# Kortex_Agro.net
KiCad netlist of a schematic drawn in EAGLE
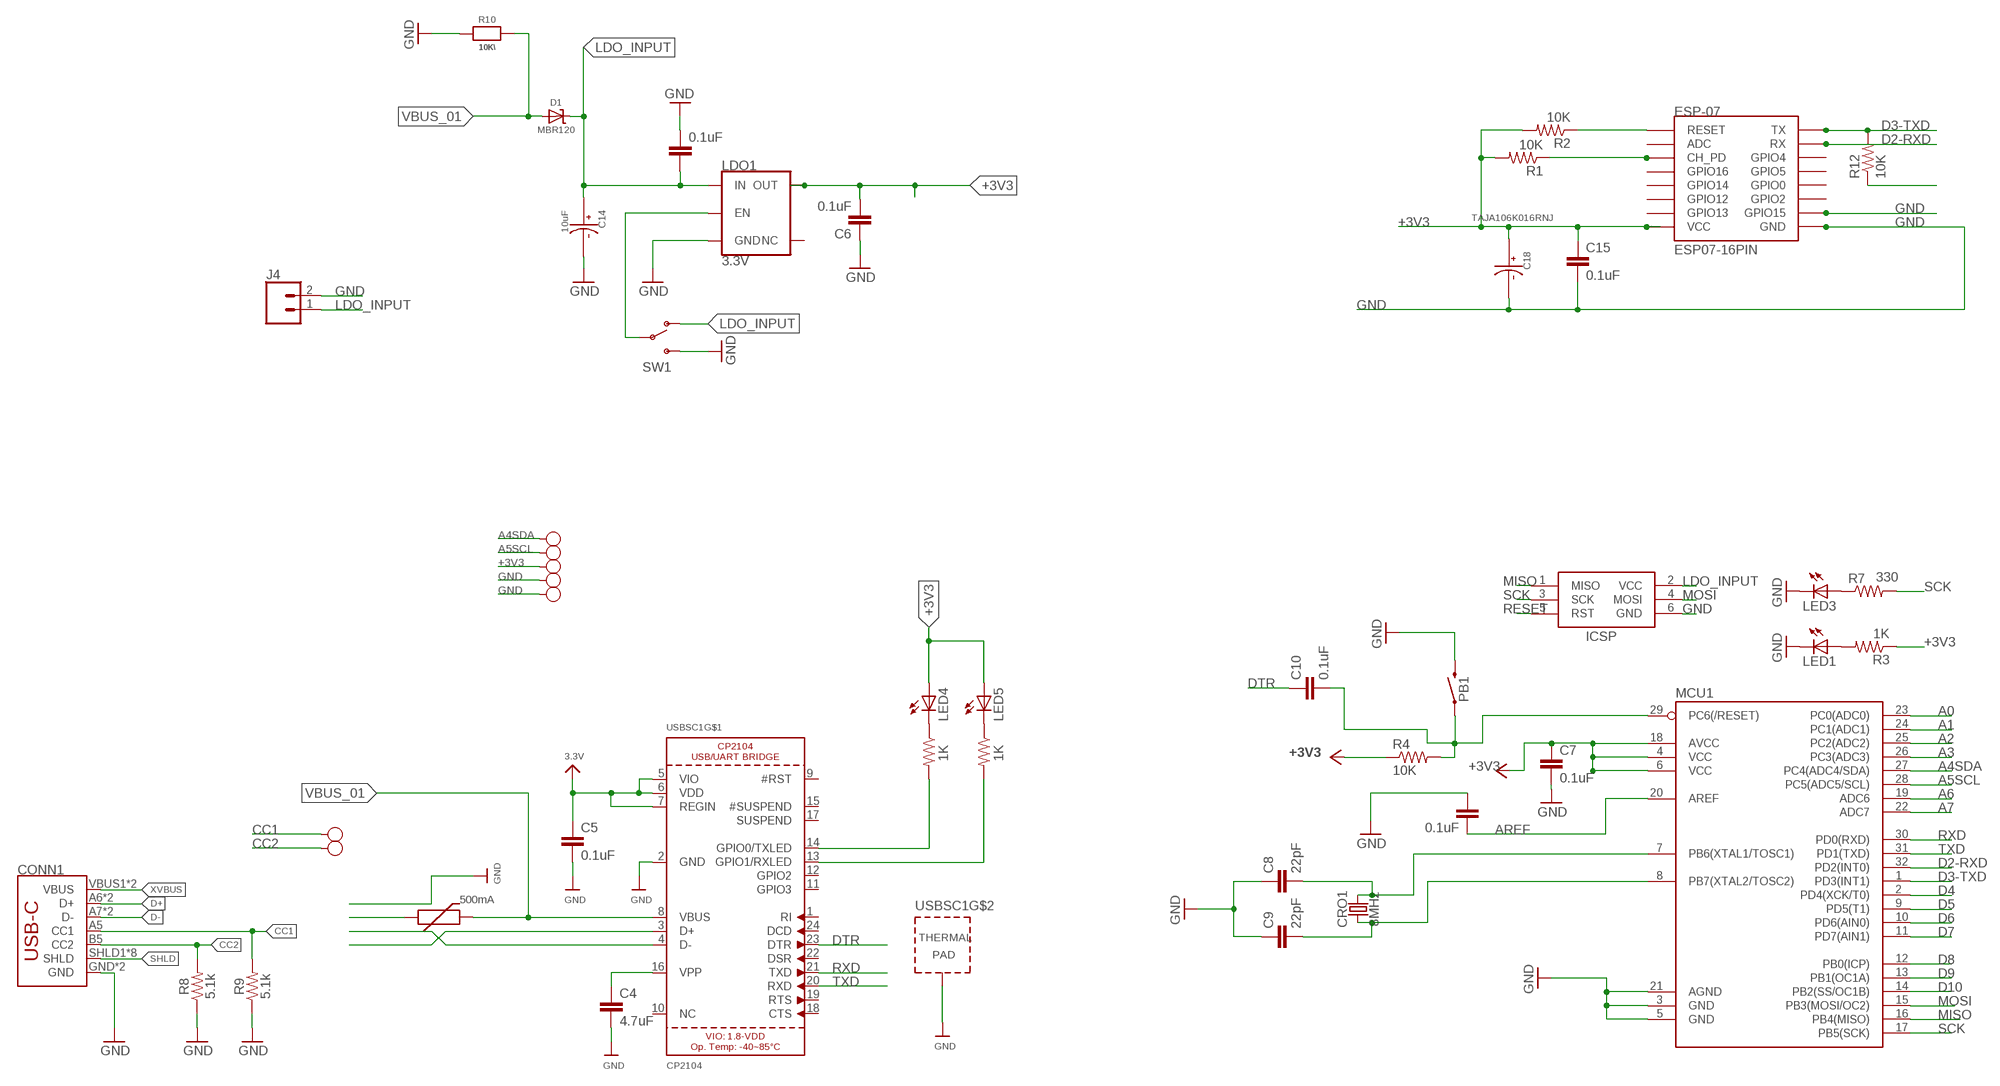
[diagram p0: schematic, sheet 1, part 1 of 2]
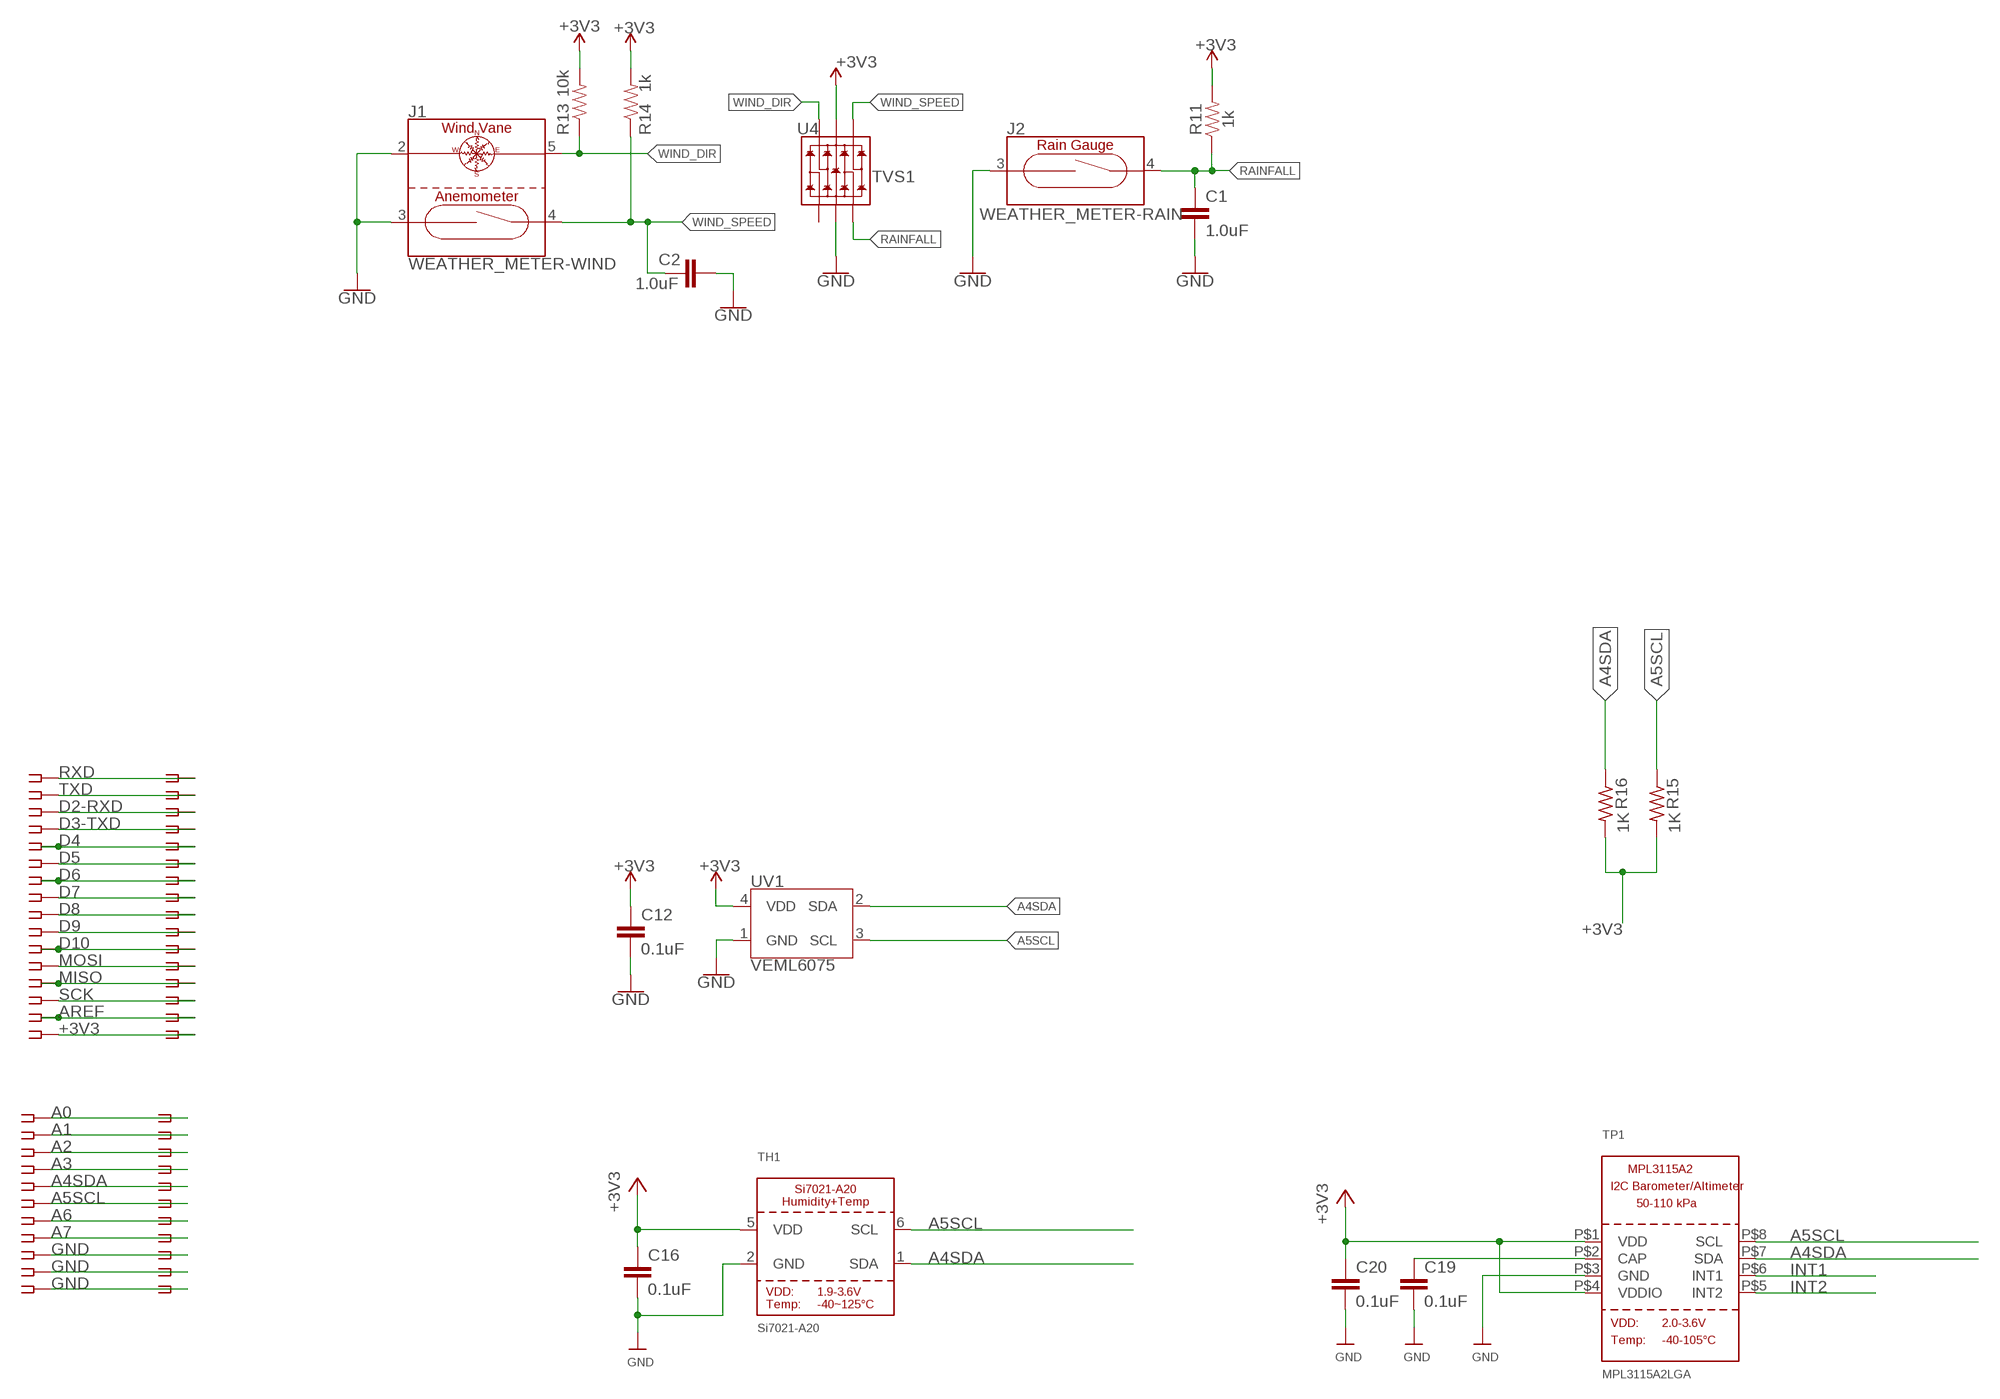
[diagram p1: schematic, sheet 1, part 2 of 2]

(export (version "E")
  (design (tool "Eeschema 10.0.6"))
  (components
    (comp (ref "+3.3V")
      (value "+3V3")
      (footprint "eagle-import:TP-D45MIL")
      (fields (field (name "PARTNO") "DNP"))
      (libsource (lib "eagle-import") (part "TEST-POINT'4545'"))
    )
    (comp (ref "C1")
      (value "1.0uF")
      (footprint "eagle-import:0603")
      (libsource (lib "eagle-import") (part "1.0UF-0603-16V-10%"))
    )
    (comp (ref "C2")
      (value "1.0uF")
      (footprint "eagle-import:0603")
      (libsource (lib "eagle-import") (part "1.0UF-0603-16V-10%"))
    )
    (comp (ref "C3")
      (value "0.1uF")
      (footprint "eagle-import:0805")
      (libsource (lib "eagle-import") (part "22UF-0805-6.3V-20%"))
    )
    (comp (ref "C4")
      (value "4.7uF")
      (footprint "eagle-import:0805")
      (libsource (lib "eagle-import") (part "22UF-0805-6.3V-20%"))
    )
    (comp (ref "C5")
      (value "0.1uF")
      (footprint "eagle-import:0805")
      (libsource (lib "eagle-import") (part "22UF-0805-6.3V-20%"))
    )
    (comp (ref "C6")
      (value "0.1uF")
      (footprint "eagle-import:0805")
      (libsource (lib "eagle-import") (part "22UF-0805-6.3V-20%"))
    )
    (comp (ref "C7")
      (value "0.1uF")
      (footprint "eagle-import:0805")
      (libsource (lib "eagle-import") (part "22UF-0805-6.3V-20%"))
    )
    (comp (ref "C8")
      (value "22pF")
      (footprint "eagle-import:0805")
      (libsource (lib "eagle-import") (part "22UF-0805-6.3V-20%"))
    )
    (comp (ref "C9")
      (value "22pF")
      (footprint "eagle-import:0805")
      (libsource (lib "eagle-import") (part "22UF-0805-6.3V-20%"))
    )
    (comp (ref "C10")
      (value "0.1uF")
      (footprint "eagle-import:0805")
      (libsource (lib "eagle-import") (part "22UF-0805-6.3V-20%"))
    )
    (comp (ref "C11")
      (value "0.1uF")
      (footprint "eagle-import:0805")
      (libsource (lib "eagle-import") (part "22UF-0805-6.3V-20%"))
    )
    (comp (ref "C12")
      (value "0.1uF")
      (footprint "eagle-import:0603")
      (libsource (lib "eagle-import") (part "0.1UF-0603-25V-(+80/-20%)"))
    )
    (comp (ref "C14")
      (value "10uF")
      (footprint "eagle-import:CAPMP3216X166")
      (fields (field (name "MF") "AVX Interconnect / Elco") (field (name "MP") "TAJA106K016RNJ"))
      (libsource (lib "eagle-import") (part "TAJA106K016RNJ"))
    )
    (comp (ref "C15")
      (value "0.1uF")
      (footprint "eagle-import:0805")
      (libsource (lib "eagle-import") (part "CAP0805"))
    )
    (comp (ref "C16")
      (value "0.1uF")
      (footprint "eagle-import:0805")
      (libsource (lib "eagle-import") (part "SparkFun-Passives_CAP0805"))
    )
    (comp (ref "C18")
      (value "TAJA106K016RNJ")
      (footprint "eagle-import:CAPMP3216X166")
      (fields (field (name "MF") "AVX Interconnect / Elco"))
      (libsource (lib "eagle-import") (part "TAJA106K016RNJ"))
    )
    (comp (ref "C19")
      (value "0.1uF")
      (footprint "eagle-import:0805")
      (libsource (lib "eagle-import") (part "SparkFun-Passives_CAP0805"))
    )
    (comp (ref "C20")
      (value "0.1uF")
      (footprint "eagle-import:0805")
      (libsource (lib "eagle-import") (part "SparkFun-Passives_CAP0805"))
    )
    (comp (ref "CONN1")
      (value "USB_C16PIN")
      (footprint "eagle-import:USB-C-16P")
      (libsource (lib "eagle-import") (part "USB_C16PIN"))
    )
    (comp (ref "CRO1")
      (value "8MHz")
      (footprint "eagle-import:CRYSTAL-SMD-5X3.2-4PAD")
      (libsource (lib "eagle-import") (part "CRYSTAL-8MHZSMD-5X3.2"))
    )
    (comp (ref "D1")
      (value "MBR120")
      (footprint "eagle-import:SOD-123")
      (libsource (lib "eagle-import") (part "DIODE-SCHOTTKYSOD-123"))
    )
    (comp (ref "ESP-07")
      (value "ESP07-16PIN")
      (footprint "eagle-import:ESP07-16PIN")
      (libsource (lib "eagle-import") (part "ESP07-16PIN"))
    )
    (comp (ref "GND")
      (value "GND")
      (footprint "eagle-import:TP-D45MIL")
      (fields (field (name "PARTNO") "DNP"))
      (libsource (lib "eagle-import") (part "TEST-POINT'4545'"))
    )
    (comp (ref "GND13")
      (value "GND")
      (footprint "eagle-import:TP-D45MIL")
      (fields (field (name "PARTNO") "DNP"))
      (libsource (lib "eagle-import") (part "TEST-POINT'4545'"))
    )
    (comp (ref "GND21")
      (value "GND")
      (footprint "eagle-import:TP-D45MIL")
      (fields (field (name "PARTNO") "DNP"))
      (libsource (lib "eagle-import") (part "TEST-POINT'4545'"))
    )
    (comp (ref "GND22")
      (value "GND")
      (footprint "eagle-import:TP-D45MIL")
      (fields (field (name "PARTNO") "DNP"))
      (libsource (lib "eagle-import") (part "TEST-POINT'4545'"))
    )
    (comp (ref "HD1")
      (value "SSW-116-02-G-D")
      (footprint "eagle-import:SSW-116-02-G-D")
      (fields (field (name "MF") "Samtec Inc."))
      (libsource (lib "eagle-import") (part "SSW-116-02-G-D"))
    )
    (comp (ref "HD2")
      (value "SSW-111-02-S-D")
      (footprint "eagle-import:SSW-111-02-S-D")
      (libsource (lib "eagle-import") (part "SSW-111-02-S-D"))
    )
    (comp (ref "ICSP")
      (value "AVRISP-6")
      (footprint "eagle-import:AVRISP")
      (libsource (lib "eagle-import") (part "AVRISP-6"))
    )
    (comp (ref "J1")
      (value "WEATHER_METER-WIND")
      (footprint "eagle-import:RJ11-6")
      (libsource (lib "eagle-import") (part "WEATHER_METER-WIND"))
    )
    (comp (ref "J2")
      (value "WEATHER_METER-RAIN")
      (footprint "eagle-import:RJ11-6")
      (libsource (lib "eagle-import") (part "WEATHER_METER-RAIN"))
    )
    (comp (ref "J4")
      (value "CONN_02")
      (footprint "eagle-import:1X02")
      (libsource (lib "eagle-import") (part "CONN_02"))
    )
    (comp (ref "LDO1")
      (value "3.3V")
      (footprint "eagle-import:SOT23-5")
      (libsource (lib "eagle-import") (part "V_REG_AP2112K-3.3V"))
    )
    (comp (ref "LED1")
      (value "LEDCHIPLED_0805")
      (footprint "eagle-import:CHIPLED_0805")
      (libsource (lib "eagle-import") (part "LEDCHIPLED_0805"))
    )
    (comp (ref "LED3")
      (value "LEDCHIPLED_0805")
      (footprint "eagle-import:CHIPLED_0805")
      (libsource (lib "eagle-import") (part "LEDCHIPLED_0805"))
    )
    (comp (ref "LED4")
      (value "LEDCHIPLED_0805")
      (footprint "eagle-import:CHIPLED_0805")
      (libsource (lib "eagle-import") (part "LEDCHIPLED_0805"))
    )
    (comp (ref "LED5")
      (value "LEDCHIPLED_0805")
      (footprint "eagle-import:CHIPLED_0805")
      (libsource (lib "eagle-import") (part "LEDCHIPLED_0805"))
    )
    (comp (ref "MCU1")
      (value "ATMEGA328P_TQFPATMEGA328P-AU")
      (footprint "eagle-import:QFP80P912X912X120-32")
      (libsource (lib "eagle-import") (part "ATMEGA328P_TQFPATMEGA328P-AU"))
    )
    (comp (ref "PB1")
      (value "SWITCH-MOMENTARY-2SMD")
      (footprint "eagle-import:TACTILE_SWITCH_SMD")
      (libsource (lib "eagle-import") (part "SWITCH-MOMENTARY-2SMD"))
    )
    (comp (ref "PTC1")
      (value "500mA")
      (footprint "eagle-import:PTC-1206")
      (libsource (lib "eagle-import") (part "PTCSMD"))
    )
    (comp (ref "R1")
      (value "10K")
      (footprint "eagle-import:M0805")
      (libsource (lib "eagle-import") (part "resistor_R-US_M0805"))
    )
    (comp (ref "R2")
      (value "10K")
      (footprint "eagle-import:M0805")
      (libsource (lib "eagle-import") (part "resistor_R-US_M0805"))
    )
    (comp (ref "R3")
      (value "1K")
      (footprint "eagle-import:M0805")
      (libsource (lib "eagle-import") (part "R-US_M0805"))
    )
    (comp (ref "R4")
      (value "10K")
      (footprint "eagle-import:M0805")
      (libsource (lib "eagle-import") (part "R-US_M0805"))
    )
    (comp (ref "R5")
      (value "1K")
      (footprint "eagle-import:M0805")
      (libsource (lib "eagle-import") (part "R-US_M0805"))
    )
    (comp (ref "R6")
      (value "1K")
      (footprint "eagle-import:M0805")
      (libsource (lib "eagle-import") (part "R-US_M0805"))
    )
    (comp (ref "R7")
      (value "330")
      (footprint "eagle-import:M0805")
      (libsource (lib "eagle-import") (part "R-US_M0805"))
    )
    (comp (ref "R8")
      (value "5.1k")
      (footprint "eagle-import:0603")
      (libsource (lib "eagle-import") (part "5.1KOHM5.1KOHM-0603-1/10W-1%"))
    )
    (comp (ref "R9")
      (value "5.1k")
      (footprint "eagle-import:0603")
      (libsource (lib "eagle-import") (part "5.1KOHM5.1KOHM-0603-1/10W-1%"))
    )
    (comp (ref "R10")
      (value "10K\\")
      (footprint "eagle-import:0805-NO")
      (libsource (lib "eagle-import") (part "RESISTOR0805_NOOUTLINE"))
    )
    (comp (ref "R11")
      (value "1k")
      (footprint "eagle-import:0603")
      (libsource (lib "eagle-import") (part "1KOHM-0603-1/10W-1%"))
    )
    (comp (ref "R12")
      (value "10K")
      (footprint "eagle-import:M0805")
      (libsource (lib "eagle-import") (part "resistor_R-US_M0805"))
    )
    (comp (ref "R13")
      (value "10k")
      (footprint "eagle-import:0603")
      (libsource (lib "eagle-import") (part "10KOHM-0603-1/10W-1%"))
    )
    (comp (ref "R14")
      (value "1k")
      (footprint "eagle-import:0603")
      (libsource (lib "eagle-import") (part "1KOHM-0603-1/10W-1%"))
    )
    (comp (ref "R15")
      (value "1K")
      (footprint "eagle-import:M0805")
      (libsource (lib "eagle-import") (part "R-US_M0805"))
    )
    (comp (ref "R16")
      (value "1K")
      (footprint "eagle-import:M0805")
      (libsource (lib "eagle-import") (part "R-US_M0805"))
    )
    (comp (ref "SCL")
      (value "SCL")
      (footprint "eagle-import:TP-D45MIL")
      (fields (field (name "PARTNO") "DNP"))
      (libsource (lib "eagle-import") (part "TEST-POINT'4545'"))
    )
    (comp (ref "SDA")
      (value "SDA")
      (footprint "eagle-import:TP-D45MIL")
      (fields (field (name "PARTNO") "DNP"))
      (libsource (lib "eagle-import") (part "TEST-POINT'4545'"))
    )
    (comp (ref "SW1")
      (value "SWITCH-SPSTSMD")
      (footprint "eagle-import:AYZ0202")
      (libsource (lib "eagle-import") (part "SWITCH-SPSTSMD"))
    )
    (comp (ref "TH1")
      (value "Si7021-A20")
      (footprint "eagle-import:DFN6_3X3_SI")
      (libsource (lib "eagle-import") (part "SI7021-A20"))
    )
    (comp (ref "TP1")
      (value "MPL3115A2LGA")
      (footprint "eagle-import:LGA8")
      (libsource (lib "eagle-import") (part "MPL3115A2LGA"))
    )
    (comp (ref "U4")
      (value "TVS1")
      (footprint "eagle-import:SOT-23-6")
      (libsource (lib "eagle-import") (part "TVS_DIODE_ARRAYSMD"))
    )
    (comp (ref "USBSC1")
      (value "CP2104")
      (footprint "eagle-import:QFN24_4MM_SMSC")
      (fields (field (name "SPICEPREFIX") "X"))
      (libsource (lib "eagle-import") (part "CP2104"))
    )
    (comp (ref "UV1")
      (value "VEML6075")
      (footprint "eagle-import:VEML6075_A3OP")
      (libsource (lib "eagle-import") (part "VEML6075"))
    )
  )
  (nets
    (net (code "1") (name "+3V3") (class "Default")
      (node (ref "+3.3V") (pin "T") (pinfunction "T_T") (pintype "bidirectional"))
      (node (ref "C12") (pin "1") (pinfunction "1_1") (pintype "passive"))
      (node (ref "C15") (pin "1") (pinfunction "1_1") (pintype "passive"))
      (node (ref "C16") (pin "1") (pinfunction "1_1") (pintype "passive"))
      (node (ref "C18") (pin "+") (pinfunction "+_+") (pintype "passive"))
      (node (ref "C20") (pin "1") (pinfunction "1_1") (pintype "passive"))
      (node (ref "C5") (pin "1") (pinfunction "1_1") (pintype "passive"))
      (node (ref "C6") (pin "2") (pinfunction "2_2") (pintype "passive"))
      (node (ref "C7") (pin "1") (pinfunction "1_1") (pintype "passive"))
      (node (ref "ESP-07") (pin "VCC") (pinfunction "VCC_VCC") (pintype "bidirectional"))
      (node (ref "HD1") (pin "31") (pinfunction "1_31") (pintype "passive"))
      (node (ref "HD1") (pin "32") (pinfunction "1_32") (pintype "passive"))
      (node (ref "LDO1") (pin "5") (pinfunction "OUT_5") (pintype "passive"))
      (node (ref "LED4") (pin "A") (pinfunction "A_A") (pintype "passive"))
      (node (ref "LED5") (pin "A") (pinfunction "A_A") (pintype "passive"))
      (node (ref "MCU1") (pin "18") (pinfunction "AVCC_18") (pintype "bidirectional"))
      (node (ref "MCU1") (pin "4") (pinfunction "VCC_4") (pintype "bidirectional"))
      (node (ref "MCU1") (pin "6") (pinfunction "VCC_6") (pintype "bidirectional"))
      (node (ref "R1") (pin "2") (pinfunction "2_2") (pintype "passive"))
      (node (ref "R11") (pin "2") (pinfunction "2_2") (pintype "passive"))
      (node (ref "R13") (pin "2") (pinfunction "2_2") (pintype "passive"))
      (node (ref "R14") (pin "2") (pinfunction "2_2") (pintype "passive"))
      (node (ref "R15") (pin "2") (pinfunction "2_2") (pintype "passive"))
      (node (ref "R16") (pin "2") (pinfunction "2_2") (pintype "passive"))
      (node (ref "R2") (pin "2") (pinfunction "2_2") (pintype "passive"))
      (node (ref "R3") (pin "1") (pinfunction "1_1") (pintype "passive"))
      (node (ref "R4") (pin "1") (pinfunction "1_1") (pintype "passive"))
      (node (ref "TH1") (pin "5") (pinfunction "VDD_5") (pintype "power_in"))
      (node (ref "TP1") (pin "P$1") (pinfunction "VDD_P$1") (pintype "power_in"))
      (node (ref "TP1") (pin "P$4") (pinfunction "VDDIO_P$4") (pintype "power_in"))
      (node (ref "U4") (pin "5") (pinfunction "VCC_5") (pintype "bidirectional"))
      (node (ref "USBSC1") (pin "5") (pinfunction "VIO_5") (pintype "power_in"))
      (node (ref "USBSC1") (pin "6") (pinfunction "VDD_6") (pintype "power_in"))
      (node (ref "USBSC1") (pin "7") (pinfunction "REGIN_7") (pintype "power_in"))
      (node (ref "UV1") (pin "4") (pinfunction "VDD_4") (pintype "bidirectional"))
    )
    (net (code "2") (name "A0") (class "Default")
      (node (ref "HD2") (pin "1") (pinfunction "1_1") (pintype "passive"))
      (node (ref "HD2") (pin "2") (pinfunction "1_2") (pintype "passive"))
      (node (ref "MCU1") (pin "23") (pinfunction "PC0(ADC0)_23") (pintype "bidirectional"))
    )
    (net (code "3") (name "A1") (class "Default")
      (node (ref "HD2") (pin "3") (pinfunction "1_3") (pintype "passive"))
      (node (ref "HD2") (pin "4") (pinfunction "1_4") (pintype "passive"))
      (node (ref "MCU1") (pin "24") (pinfunction "PC1(ADC1)_24") (pintype "bidirectional"))
    )
    (net (code "4") (name "A2") (class "Default")
      (node (ref "HD2") (pin "5") (pinfunction "1_5") (pintype "passive"))
      (node (ref "HD2") (pin "6") (pinfunction "1_6") (pintype "passive"))
      (node (ref "MCU1") (pin "25") (pinfunction "PC2(ADC2)_25") (pintype "bidirectional"))
    )
    (net (code "5") (name "A3") (class "Default")
      (node (ref "HD2") (pin "7") (pinfunction "1_7") (pintype "passive"))
      (node (ref "HD2") (pin "8") (pinfunction "1_8") (pintype "passive"))
      (node (ref "MCU1") (pin "26") (pinfunction "PC3(ADC3)_26") (pintype "bidirectional"))
    )
    (net (code "6") (name "A4SDA") (class "Default")
      (node (ref "HD2") (pin "10") (pinfunction "1_10") (pintype "passive"))
      (node (ref "HD2") (pin "9") (pinfunction "1_9") (pintype "passive"))
      (node (ref "MCU1") (pin "27") (pinfunction "PC4(ADC4/SDA)_27") (pintype "bidirectional"))
      (node (ref "R16") (pin "1") (pinfunction "1_1") (pintype "passive"))
      (node (ref "SDA") (pin "T") (pinfunction "T_T") (pintype "bidirectional"))
      (node (ref "TH1") (pin "1") (pinfunction "SDA_1") (pintype "open_collector"))
      (node (ref "TP1") (pin "P$7") (pinfunction "SDA_P$7") (pintype "bidirectional"))
      (node (ref "UV1") (pin "2") (pinfunction "SDA_2") (pintype "bidirectional"))
    )
    (net (code "7") (name "A5SCL") (class "Default")
      (node (ref "HD2") (pin "11") (pinfunction "1_11") (pintype "passive"))
      (node (ref "HD2") (pin "12") (pinfunction "1_12") (pintype "passive"))
      (node (ref "MCU1") (pin "28") (pinfunction "PC5(ADC5/SCL)_28") (pintype "bidirectional"))
      (node (ref "R15") (pin "1") (pinfunction "1_1") (pintype "passive"))
      (node (ref "SCL") (pin "T") (pinfunction "T_T") (pintype "bidirectional"))
      (node (ref "TH1") (pin "6") (pinfunction "SCL_6") (pintype "open_collector"))
      (node (ref "TP1") (pin "P$8") (pinfunction "SCL_P$8") (pintype "bidirectional"))
      (node (ref "UV1") (pin "3") (pinfunction "SCL_3") (pintype "bidirectional"))
    )
    (net (code "8") (name "A6") (class "Default")
      (node (ref "HD2") (pin "13") (pinfunction "1_13") (pintype "passive"))
      (node (ref "HD2") (pin "14") (pinfunction "1_14") (pintype "passive"))
      (node (ref "MCU1") (pin "19") (pinfunction "ADC6_19") (pintype "bidirectional"))
    )
    (net (code "9") (name "A7") (class "Default")
      (node (ref "HD2") (pin "15") (pinfunction "1_15") (pintype "passive"))
      (node (ref "HD2") (pin "16") (pinfunction "1_16") (pintype "passive"))
      (node (ref "MCU1") (pin "22") (pinfunction "ADC7_22") (pintype "bidirectional"))
    )
    (net (code "10") (name "AREF") (class "Default")
      (node (ref "C11") (pin "2") (pinfunction "2_2") (pintype "passive"))
      (node (ref "HD1") (pin "29") (pinfunction "1_29") (pintype "passive"))
      (node (ref "HD1") (pin "30") (pinfunction "1_30") (pintype "passive"))
      (node (ref "MCU1") (pin "20") (pinfunction "AREF_20") (pintype "bidirectional"))
    )
    (net (code "11") (name "CC1") (class "Default")
      (node (ref "CONN1") (pin "A5") (pinfunction "CC1_A5") (pintype "bidirectional"))
      (node (ref "GND21") (pin "T") (pinfunction "T_T") (pintype "bidirectional"))
      (node (ref "R9") (pin "2") (pinfunction "2_2") (pintype "passive"))
    )
    (net (code "12") (name "CC2") (class "Default")
      (node (ref "CONN1") (pin "B5") (pinfunction "CC2_B5") (pintype "bidirectional"))
      (node (ref "GND22") (pin "T") (pinfunction "T_T") (pintype "bidirectional"))
      (node (ref "R8") (pin "2") (pinfunction "2_2") (pintype "passive"))
    )
    (net (code "13") (name "D+") (class "Default")
      (node (ref "CONN1") (pin "A6") (pinfunction "D+_A6") (pintype "bidirectional"))
      (node (ref "CONN1") (pin "B6") (pinfunction "D+_B6") (pintype "bidirectional"))
      (node (ref "USBSC1") (pin "3") (pinfunction "D+_3") (pintype "bidirectional"))
    )
    (net (code "14") (name "D-") (class "Default")
      (node (ref "CONN1") (pin "A7") (pinfunction "D-_A7") (pintype "bidirectional"))
      (node (ref "CONN1") (pin "B7") (pinfunction "D-_B7") (pintype "bidirectional"))
      (node (ref "USBSC1") (pin "4") (pinfunction "D-_4") (pintype "bidirectional"))
    )
    (net (code "15") (name "D2-RXD") (class "Default")
      (node (ref "ESP-07") (pin "RX") (pinfunction "RX_RX") (pintype "bidirectional"))
      (node (ref "HD1") (pin "5") (pinfunction "1_5") (pintype "passive"))
      (node (ref "HD1") (pin "6") (pinfunction "1_6") (pintype "passive"))
      (node (ref "MCU1") (pin "32") (pinfunction "PD2(INT0)_32") (pintype "bidirectional"))
    )
    (net (code "16") (name "D3-TXD") (class "Default")
      (node (ref "ESP-07") (pin "TX") (pinfunction "TX_TX") (pintype "bidirectional"))
      (node (ref "HD1") (pin "7") (pinfunction "1_7") (pintype "passive"))
      (node (ref "HD1") (pin "8") (pinfunction "1_8") (pintype "passive"))
      (node (ref "MCU1") (pin "1") (pinfunction "PD3(INT1)_1") (pintype "bidirectional"))
      (node (ref "R12") (pin "2") (pinfunction "2_2") (pintype "passive"))
    )
    (net (code "17") (name "D4") (class "Default")
      (node (ref "HD1") (pin "10") (pinfunction "1_10") (pintype "passive"))
      (node (ref "HD1") (pin "9") (pinfunction "1_9") (pintype "passive"))
      (node (ref "MCU1") (pin "2") (pinfunction "PD4(XCK/T0)_2") (pintype "bidirectional"))
    )
    (net (code "18") (name "D5") (class "Default")
      (node (ref "HD1") (pin "11") (pinfunction "1_11") (pintype "passive"))
      (node (ref "HD1") (pin "12") (pinfunction "1_12") (pintype "passive"))
      (node (ref "MCU1") (pin "9") (pinfunction "PD5(T1)_9") (pintype "bidirectional"))
    )
    (net (code "19") (name "D6") (class "Default")
      (node (ref "HD1") (pin "13") (pinfunction "1_13") (pintype "passive"))
      (node (ref "HD1") (pin "14") (pinfunction "1_14") (pintype "passive"))
      (node (ref "MCU1") (pin "10") (pinfunction "PD6(AIN0)_10") (pintype "bidirectional"))
    )
    (net (code "20") (name "D7") (class "Default")
      (node (ref "HD1") (pin "15") (pinfunction "1_15") (pintype "passive"))
      (node (ref "HD1") (pin "16") (pinfunction "1_16") (pintype "passive"))
      (node (ref "MCU1") (pin "11") (pinfunction "PD7(AIN1)_11") (pintype "bidirectional"))
    )
    (net (code "21") (name "D8") (class "Default")
      (node (ref "HD1") (pin "17") (pinfunction "1_17") (pintype "passive"))
      (node (ref "HD1") (pin "18") (pinfunction "1_18") (pintype "passive"))
      (node (ref "MCU1") (pin "12") (pinfunction "PB0(ICP)_12") (pintype "bidirectional"))
    )
    (net (code "22") (name "D9") (class "Default")
      (node (ref "HD1") (pin "19") (pinfunction "1_19") (pintype "passive"))
      (node (ref "HD1") (pin "20") (pinfunction "1_20") (pintype "passive"))
      (node (ref "MCU1") (pin "13") (pinfunction "PB1(OC1A)_13") (pintype "bidirectional"))
    )
    (net (code "23") (name "D10") (class "Default")
      (node (ref "HD1") (pin "21") (pinfunction "1_21") (pintype "passive"))
      (node (ref "HD1") (pin "22") (pinfunction "1_22") (pintype "passive"))
      (node (ref "MCU1") (pin "14") (pinfunction "PB2(SS/OC1B)_14") (pintype "bidirectional"))
    )
    (net (code "24") (name "DTR") (class "Default")
      (node (ref "C10") (pin "1") (pinfunction "1_1") (pintype "passive"))
      (node (ref "USBSC1") (pin "23") (pinfunction "DTR_23") (pintype "output"))
    )
    (net (code "25") (name "GND") (class "Default")
      (node (ref "C1") (pin "2") (pinfunction "2_2") (pintype "passive"))
      (node (ref "C11") (pin "1") (pinfunction "1_1") (pintype "passive"))
      (node (ref "C12") (pin "2") (pinfunction "2_2") (pintype "passive"))
      (node (ref "C14") (pin "-") (pinfunction "-_-") (pintype "passive"))
      (node (ref "C15") (pin "2") (pinfunction "2_2") (pintype "passive"))
      (node (ref "C16") (pin "2") (pinfunction "2_2") (pintype "passive"))
      (node (ref "C18") (pin "-") (pinfunction "-_-") (pintype "passive"))
      (node (ref "C19") (pin "2") (pinfunction "2_2") (pintype "passive"))
      (node (ref "C2") (pin "2") (pinfunction "2_2") (pintype "passive"))
      (node (ref "C20") (pin "2") (pinfunction "2_2") (pintype "passive"))
      (node (ref "C3") (pin "1") (pinfunction "1_1") (pintype "passive"))
      (node (ref "C4") (pin "2") (pinfunction "2_2") (pintype "passive"))
      (node (ref "C5") (pin "2") (pinfunction "2_2") (pintype "passive"))
      (node (ref "C6") (pin "1") (pinfunction "1_1") (pintype "passive"))
      (node (ref "C7") (pin "2") (pinfunction "2_2") (pintype "passive"))
      (node (ref "C8") (pin "1") (pinfunction "1_1") (pintype "passive"))
      (node (ref "C9") (pin "1") (pinfunction "1_1") (pintype "passive"))
      (node (ref "CONN1") (pin "GND") (pinfunction "GND_GND") (pintype "bidirectional"))
      (node (ref "CONN1") (pin "GND2") (pinfunction "GND_GND2") (pintype "bidirectional"))
      (node (ref "ESP-07") (pin "GND") (pinfunction "GND_GND") (pintype "bidirectional"))
      (node (ref "ESP-07") (pin "GPIO15") (pinfunction "GPIO15_GPIO15") (pintype "bidirectional"))
      (node (ref "GND") (pin "T") (pinfunction "T_T") (pintype "bidirectional"))
      (node (ref "GND13") (pin "T") (pinfunction "T_T") (pintype "bidirectional"))
      (node (ref "HD2") (pin "17") (pinfunction "1_17") (pintype "passive"))
      (node (ref "HD2") (pin "18") (pinfunction "1_18") (pintype "passive"))
      (node (ref "HD2") (pin "19") (pinfunction "1_19") (pintype "passive"))
      (node (ref "HD2") (pin "20") (pinfunction "1_20") (pintype "passive"))
      (node (ref "HD2") (pin "21") (pinfunction "1_21") (pintype "passive"))
      (node (ref "HD2") (pin "22") (pinfunction "1_22") (pintype "passive"))
      (node (ref "ICSP") (pin "6") (pinfunction "GND_6") (pintype "power_in"))
      (node (ref "J1") (pin "2") (pinfunction "DIR-1_2") (pintype "bidirectional"))
      (node (ref "J1") (pin "3") (pinfunction "ANN-1_3") (pintype "bidirectional"))
      (node (ref "J2") (pin "3") (pinfunction "1_3") (pintype "passive"))
      (node (ref "J4") (pin "2") (pinfunction "2_2") (pintype "passive"))
      (node (ref "LDO1") (pin "2") (pinfunction "GND_2") (pintype "input"))
      (node (ref "LED1") (pin "C") (pinfunction "C_C") (pintype "passive"))
      (node (ref "LED3") (pin "C") (pinfunction "C_C") (pintype "passive"))
      (node (ref "MCU1") (pin "21") (pinfunction "AGND_21") (pintype "bidirectional"))
      (node (ref "MCU1") (pin "3") (pinfunction "GND_3") (pintype "bidirectional"))
      (node (ref "MCU1") (pin "5") (pinfunction "GND_5") (pintype "bidirectional"))
      (node (ref "PB1") (pin "3") (pinfunction "2_3") (pintype "passive"))
      (node (ref "R10") (pin "1") (pinfunction "1_1") (pintype "passive"))
      (node (ref "R8") (pin "1") (pinfunction "1_1") (pintype "passive"))
      (node (ref "R9") (pin "1") (pinfunction "1_1") (pintype "passive"))
      (node (ref "SW1") (pin "3") (pinfunction "S_3") (pintype "passive"))
      (node (ref "TH1") (pin "2") (pinfunction "GND_2") (pintype "power_in"))
      (node (ref "TP1") (pin "P$3") (pinfunction "GND_P$3") (pintype "power_in"))
      (node (ref "U4") (pin "2") (pinfunction "VSS_2") (pintype "bidirectional"))
      (node (ref "USBSC1") (pin "2") (pinfunction "GND_2") (pintype "power_in"))
      (node (ref "USBSC1") (pin "THERM") (pinfunction "TP_THERM") (pintype "power_in"))
      (node (ref "UV1") (pin "1") (pinfunction "GND_1") (pintype "bidirectional"))
    )
    (net (code "26") (name "INT1") (class "Default")
      (node (ref "TP1") (pin "P$6") (pinfunction "INT1_P$6") (pintype "output"))
    )
    (net (code "27") (name "INT2") (class "Default")
      (node (ref "TP1") (pin "P$5") (pinfunction "INT2_P$5") (pintype "output"))
    )
    (net (code "28") (name "LDO_INPUT") (class "Default")
      (node (ref "C14") (pin "+") (pinfunction "+_+") (pintype "passive"))
      (node (ref "C3") (pin "2") (pinfunction "2_2") (pintype "passive"))
      (node (ref "D1") (pin "C") (pinfunction "C_C") (pintype "passive"))
      (node (ref "ICSP") (pin "2") (pinfunction "VCC_2") (pintype "power_in"))
      (node (ref "J4") (pin "1") (pinfunction "1_1") (pintype "passive"))
      (node (ref "LDO1") (pin "1") (pinfunction "IN_1") (pintype "input"))
      (node (ref "SW1") (pin "1") (pinfunction "O_1") (pintype "passive"))
    )
    (net (code "29") (name "MISO") (class "Default")
      (node (ref "HD1") (pin "25") (pinfunction "1_25") (pintype "passive"))
      (node (ref "HD1") (pin "26") (pinfunction "1_26") (pintype "passive"))
      (node (ref "ICSP") (pin "1") (pinfunction "MISO_1") (pintype "input"))
      (node (ref "MCU1") (pin "16") (pinfunction "PB4(MISO)_16") (pintype "bidirectional"))
    )
    (net (code "30") (name "MOSI") (class "Default")
      (node (ref "HD1") (pin "23") (pinfunction "1_23") (pintype "passive"))
      (node (ref "HD1") (pin "24") (pinfunction "1_24") (pintype "passive"))
      (node (ref "ICSP") (pin "4") (pinfunction "MOSI_4") (pintype "output"))
      (node (ref "MCU1") (pin "15") (pinfunction "PB3(MOSI/OC2)_15") (pintype "bidirectional"))
    )
    (net (code "31") (name "Net-(CRO1-2)") (class "Default")
      (node (ref "C8") (pin "2") (pinfunction "2_2") (pintype "passive"))
      (node (ref "CRO1") (pin "3") (pinfunction "2_3") (pintype "passive"))
      (node (ref "MCU1") (pin "7") (pinfunction "PB6(XTAL1/TOSC1)_7") (pintype "bidirectional"))
    )
    (net (code "32") (name "Net-(ESP-07-PadCH_PD)") (class "Default")
      (node (ref "ESP-07") (pin "CH_PD") (pinfunction "CH_PD_CH_PD") (pintype "bidirectional"))
      (node (ref "R1") (pin "1") (pinfunction "1_1") (pintype "passive"))
    )
    (net (code "33") (name "Net-(ESP-07-RESET)") (class "Default")
      (node (ref "ESP-07") (pin "REST") (pinfunction "RESET_REST") (pintype "bidirectional"))
      (node (ref "R2") (pin "1") (pinfunction "1_1") (pintype "passive"))
    )
    (net (code "34") (name "Net-(LDO1-EN)") (class "Default")
      (node (ref "LDO1") (pin "3") (pinfunction "EN_3") (pintype "input"))
      (node (ref "SW1") (pin "2") (pinfunction "P_2") (pintype "passive"))
    )
    (net (code "35") (name "Net-(LED1-PadA)") (class "Default")
      (node (ref "LED1") (pin "A") (pinfunction "A_A") (pintype "passive"))
      (node (ref "R3") (pin "2") (pinfunction "2_2") (pintype "passive"))
    )
    (net (code "36") (name "Net-(LED3-PadA)") (class "Default")
      (node (ref "LED3") (pin "A") (pinfunction "A_A") (pintype "passive"))
      (node (ref "R7") (pin "1") (pinfunction "1_1") (pintype "passive"))
    )
    (net (code "37") (name "Net-(LED4-PadC)") (class "Default")
      (node (ref "LED4") (pin "C") (pinfunction "C_C") (pintype "passive"))
      (node (ref "R6") (pin "1") (pinfunction "1_1") (pintype "passive"))
    )
    (net (code "38") (name "Net-(LED5-PadC)") (class "Default")
      (node (ref "LED5") (pin "C") (pinfunction "C_C") (pintype "passive"))
      (node (ref "R5") (pin "1") (pinfunction "1_1") (pintype "passive"))
    )
    (net (code "39") (name "Net-(MCU1-PB7(XTAL2{slash}TOSC2))") (class "Default")
      (node (ref "C9") (pin "2") (pinfunction "2_2") (pintype "passive"))
      (node (ref "CRO1") (pin "1") (pinfunction "1_1") (pintype "passive"))
      (node (ref "MCU1") (pin "8") (pinfunction "PB7(XTAL2/TOSC2)_8") (pintype "bidirectional"))
    )
    (net (code "40") (name "Net-(TP1-CAP)") (class "Default")
      (node (ref "C19") (pin "1") (pinfunction "1_1") (pintype "passive"))
      (node (ref "TP1") (pin "P$2") (pinfunction "CAP_P$2") (pintype "passive"))
    )
    (net (code "41") (name "Net-(USBSC1A-GPIO0{slash}TXLED)") (class "Default")
      (node (ref "R6") (pin "2") (pinfunction "2_2") (pintype "passive"))
      (node (ref "USBSC1") (pin "14") (pinfunction "GPIO0/TXLED_14") (pintype "bidirectional"))
    )
    (net (code "42") (name "Net-(USBSC1A-GPIO1{slash}RXLED)") (class "Default")
      (node (ref "R5") (pin "2") (pinfunction "2_2") (pintype "passive"))
      (node (ref "USBSC1") (pin "13") (pinfunction "GPIO1/RXLED_13") (pintype "bidirectional"))
    )
    (net (code "43") (name "Net-(USBSC1A-VPP)") (class "Default")
      (node (ref "C4") (pin "1") (pinfunction "1_1") (pintype "passive"))
      (node (ref "USBSC1") (pin "16") (pinfunction "VPP_16") (pintype "bidirectional"))
    )
    (net (code "44") (name "RAINFALL") (class "Default")
      (node (ref "C1") (pin "1") (pinfunction "1_1") (pintype "passive"))
      (node (ref "J2") (pin "4") (pinfunction "2_4") (pintype "passive"))
      (node (ref "R11") (pin "1") (pinfunction "1_1") (pintype "passive"))
      (node (ref "U4") (pin "3") (pinfunction "IO2_3") (pintype "bidirectional"))
    )
    (net (code "45") (name "RESET") (class "Default")
      (node (ref "C10") (pin "2") (pinfunction "2_2") (pintype "passive"))
      (node (ref "ICSP") (pin "5") (pinfunction "RST_5") (pintype "output"))
      (node (ref "MCU1") (pin "29") (pinfunction "PC6(/RESET)_29") (pintype "bidirectional"))
      (node (ref "PB1") (pin "1") (pinfunction "1_1") (pintype "passive"))
      (node (ref "R4") (pin "2") (pinfunction "2_2") (pintype "passive"))
    )
    (net (code "46") (name "RXD") (class "Default")
      (node (ref "HD1") (pin "1") (pinfunction "1_1") (pintype "passive"))
      (node (ref "HD1") (pin "2") (pinfunction "1_2") (pintype "passive"))
      (node (ref "MCU1") (pin "30") (pinfunction "PD0(RXD)_30") (pintype "bidirectional"))
      (node (ref "USBSC1") (pin "21") (pinfunction "TXD_21") (pintype "output"))
    )
    (net (code "47") (name "SCK") (class "Default")
      (node (ref "HD1") (pin "27") (pinfunction "1_27") (pintype "passive"))
      (node (ref "HD1") (pin "28") (pinfunction "1_28") (pintype "passive"))
      (node (ref "ICSP") (pin "3") (pinfunction "SCK_3") (pintype "output"))
      (node (ref "MCU1") (pin "17") (pinfunction "PB5(SCK)_17") (pintype "bidirectional"))
      (node (ref "R7") (pin "2") (pinfunction "2_2") (pintype "passive"))
    )
    (net (code "48") (name "SHLD") (class "Default")
      (node (ref "CONN1") (pin "SHLD1") (pinfunction "SHLD_SHLD1") (pintype "bidirectional"))
      (node (ref "CONN1") (pin "SHLD2") (pinfunction "SHLD_SHLD2") (pintype "bidirectional"))
      (node (ref "CONN1") (pin "SHLD3") (pinfunction "SHLD_SHLD3") (pintype "bidirectional"))
      (node (ref "CONN1") (pin "SHLD4") (pinfunction "SHLD_SHLD4") (pintype "bidirectional"))
      (node (ref "CONN1") (pin "SHLD5") (pinfunction "SHLD_SHLD5") (pintype "bidirectional"))
      (node (ref "CONN1") (pin "SHLD6") (pinfunction "SHLD_SHLD6") (pintype "bidirectional"))
      (node (ref "CONN1") (pin "SHLD7") (pinfunction "SHLD_SHLD7") (pintype "bidirectional"))
      (node (ref "CONN1") (pin "SHLD8") (pinfunction "SHLD_SHLD8") (pintype "bidirectional"))
    )
    (net (code "49") (name "TXD") (class "Default")
      (node (ref "HD1") (pin "3") (pinfunction "1_3") (pintype "passive"))
      (node (ref "HD1") (pin "4") (pinfunction "1_4") (pintype "passive"))
      (node (ref "MCU1") (pin "31") (pinfunction "PD1(TXD)_31") (pintype "bidirectional"))
      (node (ref "USBSC1") (pin "20") (pinfunction "RXD_20") (pintype "input"))
    )
    (net (code "50") (name "VBUS_01") (class "Default")
      (node (ref "D1") (pin "A") (pinfunction "A_A") (pintype "passive"))
      (node (ref "PTC1") (pin "2") (pinfunction "2_2") (pintype "bidirectional"))
      (node (ref "R10") (pin "2") (pinfunction "2_2") (pintype "passive"))
      (node (ref "USBSC1") (pin "8") (pinfunction "VBUS_8") (pintype "power_in"))
    )
    (net (code "51") (name "WIND_DIR") (class "Default")
      (node (ref "J1") (pin "5") (pinfunction "DIR2_5") (pintype "bidirectional"))
      (node (ref "R13") (pin "1") (pinfunction "1_1") (pintype "passive"))
      (node (ref "U4") (pin "6") (pinfunction "IO4_6") (pintype "bidirectional"))
    )
    (net (code "52") (name "WIND_SPEED") (class "Default")
      (node (ref "C2") (pin "1") (pinfunction "1_1") (pintype "passive"))
      (node (ref "J1") (pin "4") (pinfunction "ANN-2_4") (pintype "bidirectional"))
      (node (ref "R14") (pin "1") (pinfunction "1_1") (pintype "passive"))
      (node (ref "U4") (pin "4") (pinfunction "IO3_4") (pintype "bidirectional"))
    )
    (net (code "53") (name "XVBUS") (class "Default")
      (node (ref "CONN1") (pin "VBUS1") (pinfunction "VBUS_VBUS1") (pintype "bidirectional"))
      (node (ref "CONN1") (pin "VBUS2") (pinfunction "VBUS_VBUS2") (pintype "bidirectional"))
      (node (ref "PTC1") (pin "1") (pinfunction "1_1") (pintype "bidirectional"))
    )
    (net (code "54") (name "unconnected-(ESP-07-PadADC)") (class "Default")
      (node (ref "ESP-07") (pin "ADC") (pinfunction "ADC_ADC") (pintype "bidirectional"))
    )
    (net (code "55") (name "unconnected-(ESP-07-PadGPIO0)") (class "Default")
      (node (ref "ESP-07") (pin "GPIO0") (pinfunction "GPIO0_GPIO0") (pintype "bidirectional"))
    )
    (net (code "56") (name "unconnected-(ESP-07-PadGPIO2)") (class "Default")
      (node (ref "ESP-07") (pin "GPIO2") (pinfunction "GPIO2_GPIO2") (pintype "bidirectional"))
    )
    (net (code "57") (name "unconnected-(ESP-07-PadGPIO4)") (class "Default")
      (node (ref "ESP-07") (pin "GPIO4") (pinfunction "GPIO4_GPIO4") (pintype "bidirectional"))
    )
    (net (code "58") (name "unconnected-(ESP-07-PadGPIO5)") (class "Default")
      (node (ref "ESP-07") (pin "GPIO5") (pinfunction "GPIO5_GPIO5") (pintype "bidirectional"))
    )
    (net (code "59") (name "unconnected-(ESP-07-PadGPIO12)") (class "Default")
      (node (ref "ESP-07") (pin "GPIO12") (pinfunction "GPIO12_GPIO12") (pintype "bidirectional"))
    )
    (net (code "60") (name "unconnected-(ESP-07-PadGPIO13)") (class "Default")
      (node (ref "ESP-07") (pin "GPIO13") (pinfunction "GPIO13_GPIO13") (pintype "bidirectional"))
    )
    (net (code "61") (name "unconnected-(ESP-07-PadGPIO14)") (class "Default")
      (node (ref "ESP-07") (pin "GPIO14") (pinfunction "GPIO14_GPIO14") (pintype "bidirectional"))
    )
    (net (code "62") (name "unconnected-(ESP-07-PadGPIO16)") (class "Default")
      (node (ref "ESP-07") (pin "GPIO16") (pinfunction "GPIO16_GPIO16") (pintype "bidirectional"))
    )
    (net (code "63") (name "unconnected-(LDO1-NC-Pad4)") (class "Default")
      (node (ref "LDO1") (pin "4") (pinfunction "NC_4") (pintype "no_connect"))
    )
    (net (code "64") (name "unconnected-(R12-Pad1)") (class "Default")
      (node (ref "R12") (pin "1") (pinfunction "1_1") (pintype "passive"))
    )
    (net (code "65") (name "unconnected-(U4-IO1-Pad1)") (class "Default")
      (node (ref "U4") (pin "1") (pinfunction "IO1_1") (pintype "bidirectional"))
    )
    (net (code "66") (name "unconnected-(USBSC1A-#RST-Pad9)") (class "Default")
      (node (ref "USBSC1") (pin "9") (pinfunction "#RST_9") (pintype "bidirectional"))
    )
    (net (code "67") (name "unconnected-(USBSC1A-#SUSPEND-Pad15)") (class "Default")
      (node (ref "USBSC1") (pin "15") (pinfunction "#SUSPEND_15") (pintype "output"))
    )
    (net (code "68") (name "unconnected-(USBSC1A-CTS-Pad18)") (class "Default")
      (node (ref "USBSC1") (pin "18") (pinfunction "CTS_18") (pintype "input"))
    )
    (net (code "69") (name "unconnected-(USBSC1A-DCD-Pad24)") (class "Default")
      (node (ref "USBSC1") (pin "24") (pinfunction "DCD_24") (pintype "input"))
    )
    (net (code "70") (name "unconnected-(USBSC1A-DSR-Pad22)") (class "Default")
      (node (ref "USBSC1") (pin "22") (pinfunction "DSR_22") (pintype "input"))
    )
    (net (code "71") (name "unconnected-(USBSC1A-GPIO2-Pad12)") (class "Default")
      (node (ref "USBSC1") (pin "12") (pinfunction "GPIO2_12") (pintype "bidirectional"))
    )
    (net (code "72") (name "unconnected-(USBSC1A-GPIO3-Pad11)") (class "Default")
      (node (ref "USBSC1") (pin "11") (pinfunction "GPIO3_11") (pintype "bidirectional"))
    )
    (net (code "73") (name "unconnected-(USBSC1A-NC-Pad10)") (class "Default")
      (node (ref "USBSC1") (pin "10") (pinfunction "NC_10") (pintype "no_connect"))
    )
    (net (code "74") (name "unconnected-(USBSC1A-RI-Pad1)") (class "Default")
      (node (ref "USBSC1") (pin "1") (pinfunction "RI_1") (pintype "input"))
    )
    (net (code "75") (name "unconnected-(USBSC1A-RTS-Pad19)") (class "Default")
      (node (ref "USBSC1") (pin "19") (pinfunction "RTS_19") (pintype "output"))
    )
    (net (code "76") (name "unconnected-(USBSC1A-SUSPEND-Pad17)") (class "Default")
      (node (ref "USBSC1") (pin "17") (pinfunction "SUSPEND_17") (pintype "output"))
    )
  )
)
